# Standalone_Kaleidoscope_8085_MPU_BOARD_V.net
KiCad netlist of a schematic drawn in EAGLE
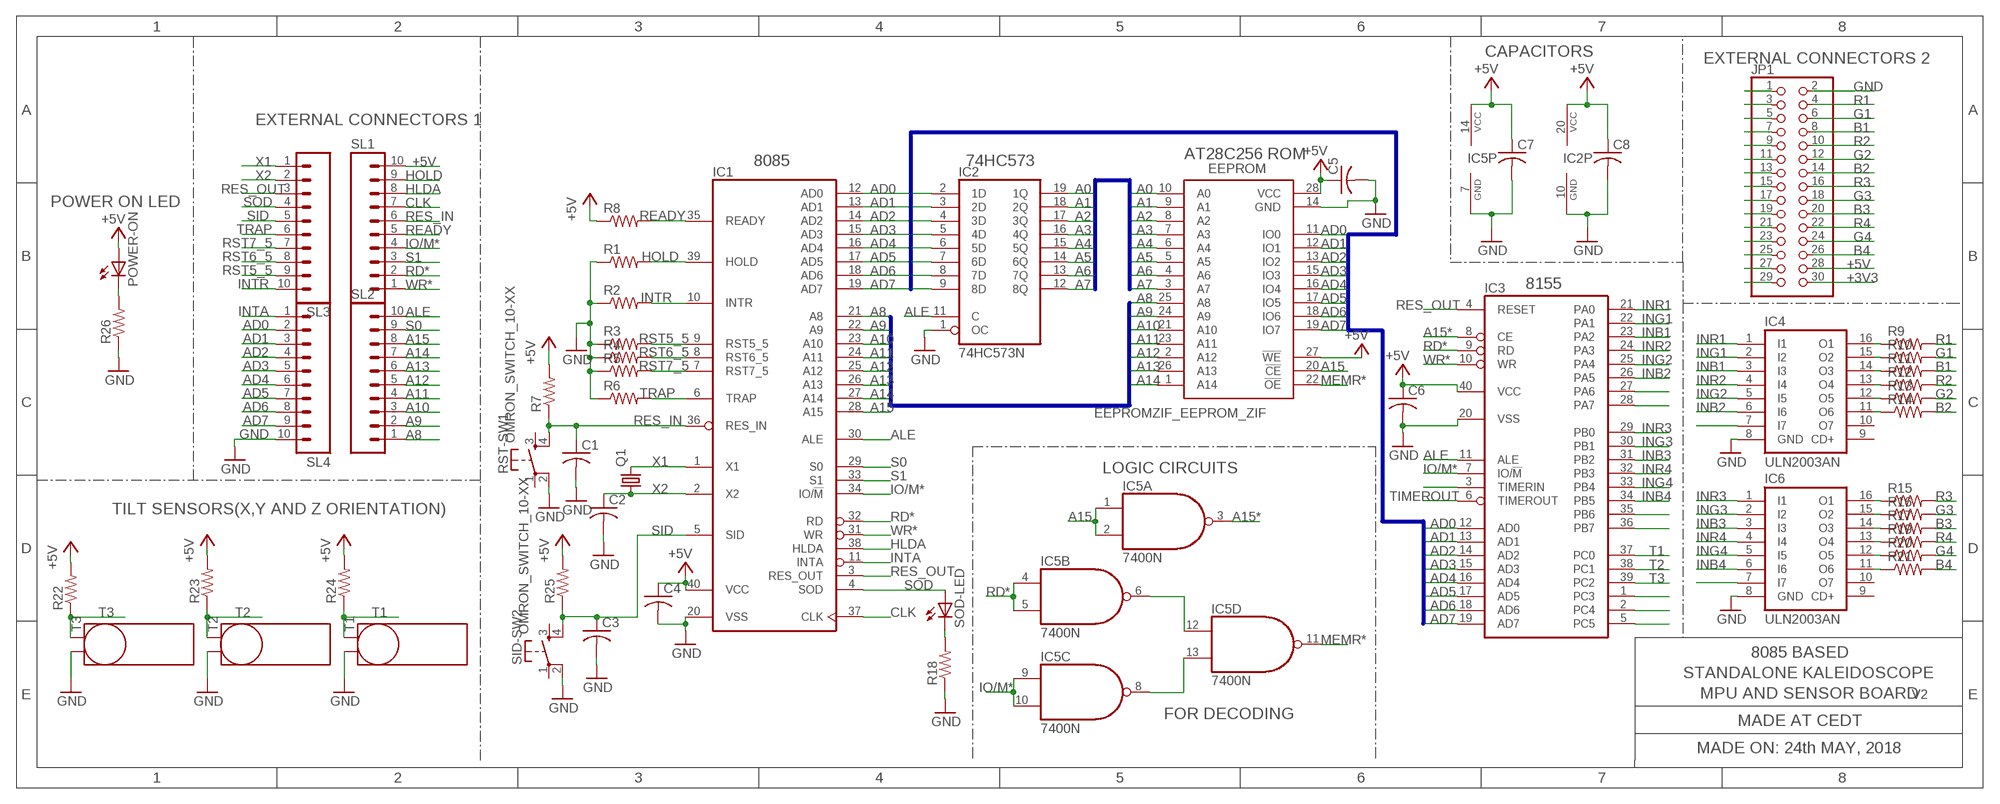
[diagram p0: schematic, sheet 1]

(export (version "E")
  (design (tool "Eeschema 10.0.6"))
  (components
    (comp (ref "C1")
      (value "C-USC0805K")
      (footprint "eagle-import:C0805K")
      (libsource (lib "eagle-import") (part "C-USC0805K"))
    )
    (comp (ref "C2")
      (value "C-USC0805K")
      (footprint "eagle-import:C0805K")
      (libsource (lib "eagle-import") (part "C-USC0805K"))
    )
    (comp (ref "C3")
      (value "C-USC0805K")
      (footprint "eagle-import:C0805K")
      (libsource (lib "eagle-import") (part "C-USC0805K"))
    )
    (comp (ref "C4")
      (value "C-USC0805K")
      (footprint "eagle-import:C0805K")
      (libsource (lib "eagle-import") (part "C-USC0805K"))
    )
    (comp (ref "C5")
      (value "C-USC0805K")
      (footprint "eagle-import:C0805K")
      (libsource (lib "eagle-import") (part "C-USC0805K"))
    )
    (comp (ref "C6")
      (value "C-USC0805K")
      (footprint "eagle-import:C0805K")
      (libsource (lib "eagle-import") (part "C-USC0805K"))
    )
    (comp (ref "C7")
      (value "C-USC0805")
      (footprint "eagle-import:C0805")
      (libsource (lib "eagle-import") (part "C-USC0805"))
    )
    (comp (ref "C8")
      (value "C-USC0805")
      (footprint "eagle-import:C0805")
      (libsource (lib "eagle-import") (part "C-USC0805"))
    )
    (comp (ref "EEPROM")
      (value "EEPROMZIF_EEPROM_ZIF")
      (footprint "eagle-import:EEPROMZIF_DIL28-6-ZIF_SOCKET")
      (libsource (lib "eagle-import") (part "EEPROMZIF_EEPROM_ZIF"))
    )
    (comp (ref "IC1")
      (value "8085")
      (footprint "eagle-import:DIL40")
      (libsource (lib "eagle-import") (part "8085"))
    )
    (comp (ref "IC2")
      (value "74HC573N")
      (footprint "eagle-import:DIL20")
      (libsource (lib "eagle-import") (part "74573NHC"))
    )
    (comp (ref "IC3")
      (value "8155")
      (footprint "eagle-import:DIL40")
      (libsource (lib "eagle-import") (part "8155"))
    )
    (comp (ref "IC4")
      (value "ULN2003AN")
      (footprint "eagle-import:DIL16")
      (libsource (lib "eagle-import") (part "ULN2003AN"))
    )
    (comp (ref "IC5")
      (value "7400N")
      (footprint "eagle-import:DIL14")
      (libsource (lib "eagle-import") (part "7400N"))
    )
    (comp (ref "IC6")
      (value "ULN2003AN")
      (footprint "eagle-import:DIL16")
      (libsource (lib "eagle-import") (part "ULN2003AN"))
    )
    (comp (ref "JP1")
      (value "PINHD-2X15")
      (footprint "eagle-import:2X15")
      (libsource (lib "eagle-import") (part "PINHD-2X15"))
    )
    (comp (ref "POWER-ON")
      (value "LEDCHIP-LED0805")
      (footprint "eagle-import:CHIP-LED0805")
      (libsource (lib "eagle-import") (part "LEDCHIP-LED0805"))
    )
    (comp (ref "Q1")
      (value "CEDT_JANUARY_2015_V5_A_CRYSTALHC49US")
      (footprint "eagle-import:CEDT_JANUARY_2015_V5_A_HC49US")
      (libsource (lib "eagle-import") (part "CEDT_JANUARY_2015_V5_A_CRYSTALHC49US"))
    )
    (comp (ref "R1")
      (value "R-US_R0805")
      (footprint "eagle-import:R0805")
      (libsource (lib "eagle-import") (part "R-US_R0805"))
    )
    (comp (ref "R2")
      (value "R-US_R0805")
      (footprint "eagle-import:R0805")
      (libsource (lib "eagle-import") (part "R-US_R0805"))
    )
    (comp (ref "R3")
      (value "R-US_R0805")
      (footprint "eagle-import:R0805")
      (libsource (lib "eagle-import") (part "R-US_R0805"))
    )
    (comp (ref "R4")
      (value "R-US_R0805")
      (footprint "eagle-import:R0805")
      (libsource (lib "eagle-import") (part "R-US_R0805"))
    )
    (comp (ref "R5")
      (value "R-US_R0805")
      (footprint "eagle-import:R0805")
      (libsource (lib "eagle-import") (part "R-US_R0805"))
    )
    (comp (ref "R6")
      (value "R-US_R0805")
      (footprint "eagle-import:R0805")
      (libsource (lib "eagle-import") (part "R-US_R0805"))
    )
    (comp (ref "R7")
      (value "R-US_R0805")
      (footprint "eagle-import:R0805")
      (libsource (lib "eagle-import") (part "R-US_R0805"))
    )
    (comp (ref "R8")
      (value "R-US_R0805")
      (footprint "eagle-import:R0805")
      (libsource (lib "eagle-import") (part "R-US_R0805"))
    )
    (comp (ref "R9")
      (value "R-US_R0805")
      (footprint "eagle-import:R0805")
      (libsource (lib "eagle-import") (part "R-US_R0805"))
    )
    (comp (ref "R10")
      (value "R-US_R0805")
      (footprint "eagle-import:R0805")
      (libsource (lib "eagle-import") (part "R-US_R0805"))
    )
    (comp (ref "R11")
      (value "R-US_R0805")
      (footprint "eagle-import:R0805")
      (libsource (lib "eagle-import") (part "R-US_R0805"))
    )
    (comp (ref "R12")
      (value "R-US_R0805")
      (footprint "eagle-import:R0805")
      (libsource (lib "eagle-import") (part "R-US_R0805"))
    )
    (comp (ref "R13")
      (value "R-US_R0805")
      (footprint "eagle-import:R0805")
      (libsource (lib "eagle-import") (part "R-US_R0805"))
    )
    (comp (ref "R14")
      (value "R-US_R0805")
      (footprint "eagle-import:R0805")
      (libsource (lib "eagle-import") (part "R-US_R0805"))
    )
    (comp (ref "R15")
      (value "R-US_R0805")
      (footprint "eagle-import:R0805")
      (libsource (lib "eagle-import") (part "R-US_R0805"))
    )
    (comp (ref "R16")
      (value "R-US_R0805")
      (footprint "eagle-import:R0805")
      (libsource (lib "eagle-import") (part "R-US_R0805"))
    )
    (comp (ref "R17")
      (value "R-US_R0805")
      (footprint "eagle-import:R0805")
      (libsource (lib "eagle-import") (part "R-US_R0805"))
    )
    (comp (ref "R18")
      (value "R-US_R0805")
      (footprint "eagle-import:R0805")
      (libsource (lib "eagle-import") (part "R-US_R0805"))
    )
    (comp (ref "R19")
      (value "R-US_R0805")
      (footprint "eagle-import:R0805")
      (libsource (lib "eagle-import") (part "R-US_R0805"))
    )
    (comp (ref "R20")
      (value "R-US_R0805")
      (footprint "eagle-import:R0805")
      (libsource (lib "eagle-import") (part "R-US_R0805"))
    )
    (comp (ref "R21")
      (value "R-US_R0805")
      (footprint "eagle-import:R0805")
      (libsource (lib "eagle-import") (part "R-US_R0805"))
    )
    (comp (ref "R22")
      (value "R-US_R0805")
      (footprint "eagle-import:R0805")
      (libsource (lib "eagle-import") (part "R-US_R0805"))
    )
    (comp (ref "R23")
      (value "R-US_R0805")
      (footprint "eagle-import:R0805")
      (libsource (lib "eagle-import") (part "R-US_R0805"))
    )
    (comp (ref "R24")
      (value "R-US_R0805")
      (footprint "eagle-import:R0805")
      (libsource (lib "eagle-import") (part "R-US_R0805"))
    )
    (comp (ref "R25")
      (value "R-US_R0805")
      (footprint "eagle-import:R0805")
      (libsource (lib "eagle-import") (part "R-US_R0805"))
    )
    (comp (ref "R26")
      (value "R-US_R0805")
      (footprint "eagle-import:R0805")
      (libsource (lib "eagle-import") (part "R-US_R0805"))
    )
    (comp (ref "RST-SW1")
      (value "OMRON_SWITCH_10-XX")
      (footprint "eagle-import:B3F-10XX")
      (libsource (lib "eagle-import") (part "OMRON_SWITCH_10-XX"))
    )
    (comp (ref "SID-SW2")
      (value "OMRON_SWITCH_10-XX")
      (footprint "eagle-import:B3F-10XX")
      (libsource (lib "eagle-import") (part "OMRON_SWITCH_10-XX"))
    )
    (comp (ref "SL1")
      (value "CON-AMP-QUICK_M10")
      (footprint "eagle-import:CON-AMP-QUICK_10P")
      (libsource (lib "eagle-import") (part "CON-AMP-QUICK_M10"))
    )
    (comp (ref "SL2")
      (value "CON-AMP-QUICK_M10")
      (footprint "eagle-import:CON-AMP-QUICK_10P")
      (libsource (lib "eagle-import") (part "CON-AMP-QUICK_M10"))
    )
    (comp (ref "SL3")
      (value "CON-AMP-QUICK_M10")
      (footprint "eagle-import:CON-AMP-QUICK_10P")
      (libsource (lib "eagle-import") (part "CON-AMP-QUICK_M10"))
    )
    (comp (ref "SL4")
      (value "CON-AMP-QUICK_M10")
      (footprint "eagle-import:CON-AMP-QUICK_10P")
      (libsource (lib "eagle-import") (part "CON-AMP-QUICK_M10"))
    )
    (comp (ref "SOD-LED")
      (value "LEDCHIP-LED0805")
      (footprint "eagle-import:CHIP-LED0805")
      (libsource (lib "eagle-import") (part "LEDCHIP-LED0805"))
    )
    (comp (ref "T1")
      (value "TILTSENSORE2.5-7")
      (footprint "eagle-import:TILTSENSOR")
      (libsource (lib "eagle-import") (part "TILTSENSORE2.5-7"))
    )
    (comp (ref "T2")
      (value "TILTSENSORE2.5-7")
      (footprint "eagle-import:TILTSENSOR")
      (libsource (lib "eagle-import") (part "TILTSENSORE2.5-7"))
    )
    (comp (ref "T3")
      (value "TILTSENSORE2.5-7")
      (footprint "eagle-import:TILTSENSOR")
      (libsource (lib "eagle-import") (part "TILTSENSORE2.5-7"))
    )
  )
  (nets
    (net (code "1") (name "+5V") (class "Default")
      (node (ref "C4") (pin "1") (pinfunction "1_1") (pintype "passive"))
      (node (ref "C5") (pin "1") (pinfunction "1_1") (pintype "passive"))
      (node (ref "C6") (pin "1") (pinfunction "1_1") (pintype "passive"))
      (node (ref "C7") (pin "1") (pinfunction "1_1") (pintype "passive"))
      (node (ref "C8") (pin "1") (pinfunction "1_1") (pintype "passive"))
      (node (ref "EEPROM") (pin "27") (pinfunction "~{WE}_27") (pintype "bidirectional"))
      (node (ref "EEPROM") (pin "28") (pinfunction "VCC_28") (pintype "bidirectional"))
      (node (ref "IC1") (pin "40") (pinfunction "VCC_40") (pintype "power_in"))
      (node (ref "IC2") (pin "20") (pinfunction "VCC_20") (pintype "power_in"))
      (node (ref "IC3") (pin "40") (pinfunction "VCC_40") (pintype "power_in"))
      (node (ref "IC5") (pin "14") (pinfunction "VCC_14") (pintype "power_in"))
      (node (ref "JP1") (pin "27") (pinfunction "27_27") (pintype "passive"))
      (node (ref "JP1") (pin "28") (pinfunction "28_28") (pintype "passive"))
      (node (ref "POWER-ON") (pin "A") (pinfunction "A_A") (pintype "passive"))
      (node (ref "R22") (pin "2") (pinfunction "2_2") (pintype "passive"))
      (node (ref "R23") (pin "2") (pinfunction "2_2") (pintype "passive"))
      (node (ref "R24") (pin "2") (pinfunction "2_2") (pintype "passive"))
      (node (ref "R25") (pin "2") (pinfunction "2_2") (pintype "passive"))
      (node (ref "R7") (pin "2") (pinfunction "2_2") (pintype "passive"))
      (node (ref "R8") (pin "1") (pinfunction "1_1") (pintype "passive"))
      (node (ref "SL1") (pin "10") (pinfunction "10_10") (pintype "passive"))
    )
    (net (code "2") (name "/+3V3") (class "Default")
      (node (ref "JP1") (pin "29") (pinfunction "29_29") (pintype "passive"))
      (node (ref "JP1") (pin "30") (pinfunction "30_30") (pintype "passive"))
    )
    (net (code "3") (name "/A0") (class "Default")
      (node (ref "EEPROM") (pin "10") (pinfunction "A0_10") (pintype "bidirectional"))
      (node (ref "IC2") (pin "19") (pinfunction "1Q_19") (pintype "tri_state"))
    )
    (net (code "4") (name "/A1") (class "Default")
      (node (ref "EEPROM") (pin "9") (pinfunction "A1_9") (pintype "bidirectional"))
      (node (ref "IC2") (pin "18") (pinfunction "2Q_18") (pintype "tri_state"))
    )
    (net (code "5") (name "/A2") (class "Default")
      (node (ref "EEPROM") (pin "8") (pinfunction "A2_8") (pintype "bidirectional"))
      (node (ref "IC2") (pin "17") (pinfunction "3Q_17") (pintype "tri_state"))
    )
    (net (code "6") (name "/A3") (class "Default")
      (node (ref "EEPROM") (pin "7") (pinfunction "A3_7") (pintype "bidirectional"))
      (node (ref "IC2") (pin "16") (pinfunction "4Q_16") (pintype "tri_state"))
    )
    (net (code "7") (name "/A4") (class "Default")
      (node (ref "EEPROM") (pin "6") (pinfunction "A4_6") (pintype "bidirectional"))
      (node (ref "IC2") (pin "15") (pinfunction "5Q_15") (pintype "tri_state"))
    )
    (net (code "8") (name "/A5") (class "Default")
      (node (ref "EEPROM") (pin "5") (pinfunction "A5_5") (pintype "bidirectional"))
      (node (ref "IC2") (pin "14") (pinfunction "6Q_14") (pintype "tri_state"))
    )
    (net (code "9") (name "/A6") (class "Default")
      (node (ref "EEPROM") (pin "4") (pinfunction "A6_4") (pintype "bidirectional"))
      (node (ref "IC2") (pin "13") (pinfunction "7Q_13") (pintype "tri_state"))
    )
    (net (code "10") (name "/A7") (class "Default")
      (node (ref "EEPROM") (pin "3") (pinfunction "A7_3") (pintype "bidirectional"))
      (node (ref "IC2") (pin "12") (pinfunction "8Q_12") (pintype "tri_state"))
    )
    (net (code "11") (name "/A8") (class "Default")
      (node (ref "EEPROM") (pin "25") (pinfunction "A8_25") (pintype "bidirectional"))
      (node (ref "IC1") (pin "21") (pinfunction "A8_21") (pintype "output"))
      (node (ref "SL2") (pin "1") (pinfunction "1_1") (pintype "passive"))
    )
    (net (code "12") (name "/A9") (class "Default")
      (node (ref "EEPROM") (pin "24") (pinfunction "A9_24") (pintype "bidirectional"))
      (node (ref "IC1") (pin "22") (pinfunction "A9_22") (pintype "output"))
      (node (ref "SL2") (pin "2") (pinfunction "2_2") (pintype "passive"))
    )
    (net (code "13") (name "/A10") (class "Default")
      (node (ref "EEPROM") (pin "21") (pinfunction "A10_21") (pintype "bidirectional"))
      (node (ref "IC1") (pin "23") (pinfunction "A10_23") (pintype "output"))
      (node (ref "SL2") (pin "3") (pinfunction "3_3") (pintype "passive"))
    )
    (net (code "14") (name "/A11") (class "Default")
      (node (ref "EEPROM") (pin "23") (pinfunction "A11_23") (pintype "bidirectional"))
      (node (ref "IC1") (pin "24") (pinfunction "A11_24") (pintype "output"))
      (node (ref "SL2") (pin "4") (pinfunction "4_4") (pintype "passive"))
    )
    (net (code "15") (name "/A12") (class "Default")
      (node (ref "EEPROM") (pin "2") (pinfunction "A12_2") (pintype "bidirectional"))
      (node (ref "IC1") (pin "25") (pinfunction "A12_25") (pintype "output"))
      (node (ref "SL2") (pin "5") (pinfunction "5_5") (pintype "passive"))
    )
    (net (code "16") (name "/A13") (class "Default")
      (node (ref "EEPROM") (pin "26") (pinfunction "A13_26") (pintype "bidirectional"))
      (node (ref "IC1") (pin "26") (pinfunction "A13_26") (pintype "output"))
      (node (ref "SL2") (pin "6") (pinfunction "6_6") (pintype "passive"))
    )
    (net (code "17") (name "/A14") (class "Default")
      (node (ref "EEPROM") (pin "1") (pinfunction "A14_1") (pintype "bidirectional"))
      (node (ref "IC1") (pin "27") (pinfunction "A14_27") (pintype "output"))
      (node (ref "SL2") (pin "7") (pinfunction "7_7") (pintype "passive"))
    )
    (net (code "18") (name "/A15") (class "Default")
      (node (ref "EEPROM") (pin "20") (pinfunction "~{CE}_20") (pintype "bidirectional"))
      (node (ref "IC1") (pin "28") (pinfunction "A15_28") (pintype "output"))
      (node (ref "IC5") (pin "1") (pinfunction "I0_1") (pintype "input"))
      (node (ref "IC5") (pin "2") (pinfunction "I1_2") (pintype "input"))
      (node (ref "SL2") (pin "8") (pinfunction "8_8") (pintype "passive"))
    )
    (net (code "19") (name "/A15*") (class "Default")
      (node (ref "IC3") (pin "8") (pinfunction "CE_8") (pintype "input"))
      (node (ref "IC5") (pin "3") (pinfunction "O_3") (pintype "output"))
    )
    (net (code "20") (name "/AD0") (class "Default")
      (node (ref "EEPROM") (pin "11") (pinfunction "IO0_11") (pintype "bidirectional"))
      (node (ref "IC1") (pin "12") (pinfunction "AD0_12") (pintype "bidirectional"))
      (node (ref "IC2") (pin "2") (pinfunction "1D_2") (pintype "input"))
      (node (ref "IC3") (pin "12") (pinfunction "AD0_12") (pintype "bidirectional"))
      (node (ref "SL4") (pin "2") (pinfunction "2_2") (pintype "passive"))
    )
    (net (code "21") (name "/AD1") (class "Default")
      (node (ref "EEPROM") (pin "12") (pinfunction "IO1_12") (pintype "bidirectional"))
      (node (ref "IC1") (pin "13") (pinfunction "AD1_13") (pintype "bidirectional"))
      (node (ref "IC2") (pin "3") (pinfunction "2D_3") (pintype "input"))
      (node (ref "IC3") (pin "13") (pinfunction "AD1_13") (pintype "bidirectional"))
      (node (ref "SL4") (pin "3") (pinfunction "3_3") (pintype "passive"))
    )
    (net (code "22") (name "/AD2") (class "Default")
      (node (ref "EEPROM") (pin "13") (pinfunction "IO2_13") (pintype "bidirectional"))
      (node (ref "IC1") (pin "14") (pinfunction "AD2_14") (pintype "bidirectional"))
      (node (ref "IC2") (pin "4") (pinfunction "3D_4") (pintype "input"))
      (node (ref "IC3") (pin "14") (pinfunction "AD2_14") (pintype "bidirectional"))
      (node (ref "SL4") (pin "4") (pinfunction "4_4") (pintype "passive"))
    )
    (net (code "23") (name "/AD3") (class "Default")
      (node (ref "EEPROM") (pin "15") (pinfunction "IO3_15") (pintype "bidirectional"))
      (node (ref "IC1") (pin "15") (pinfunction "AD3_15") (pintype "bidirectional"))
      (node (ref "IC2") (pin "5") (pinfunction "4D_5") (pintype "input"))
      (node (ref "IC3") (pin "15") (pinfunction "AD3_15") (pintype "bidirectional"))
      (node (ref "SL4") (pin "5") (pinfunction "5_5") (pintype "passive"))
    )
    (net (code "24") (name "/AD4") (class "Default")
      (node (ref "EEPROM") (pin "16") (pinfunction "IO4_16") (pintype "bidirectional"))
      (node (ref "IC1") (pin "16") (pinfunction "AD4_16") (pintype "bidirectional"))
      (node (ref "IC2") (pin "6") (pinfunction "5D_6") (pintype "input"))
      (node (ref "IC3") (pin "16") (pinfunction "AD4_16") (pintype "bidirectional"))
      (node (ref "SL4") (pin "6") (pinfunction "6_6") (pintype "passive"))
    )
    (net (code "25") (name "/AD5") (class "Default")
      (node (ref "EEPROM") (pin "17") (pinfunction "IO5_17") (pintype "bidirectional"))
      (node (ref "IC1") (pin "17") (pinfunction "AD5_17") (pintype "bidirectional"))
      (node (ref "IC2") (pin "7") (pinfunction "6D_7") (pintype "input"))
      (node (ref "IC3") (pin "17") (pinfunction "AD5_17") (pintype "bidirectional"))
      (node (ref "SL4") (pin "7") (pinfunction "7_7") (pintype "passive"))
    )
    (net (code "26") (name "/AD6") (class "Default")
      (node (ref "EEPROM") (pin "18") (pinfunction "IO6_18") (pintype "bidirectional"))
      (node (ref "IC1") (pin "18") (pinfunction "AD6_18") (pintype "bidirectional"))
      (node (ref "IC2") (pin "8") (pinfunction "7D_8") (pintype "input"))
      (node (ref "IC3") (pin "18") (pinfunction "AD6_18") (pintype "bidirectional"))
      (node (ref "SL4") (pin "8") (pinfunction "8_8") (pintype "passive"))
    )
    (net (code "27") (name "/AD7") (class "Default")
      (node (ref "EEPROM") (pin "19") (pinfunction "IO7_19") (pintype "bidirectional"))
      (node (ref "IC1") (pin "19") (pinfunction "AD7_19") (pintype "bidirectional"))
      (node (ref "IC2") (pin "9") (pinfunction "8D_9") (pintype "input"))
      (node (ref "IC3") (pin "19") (pinfunction "AD7_19") (pintype "bidirectional"))
      (node (ref "SL4") (pin "9") (pinfunction "9_9") (pintype "passive"))
    )
    (net (code "28") (name "/ALE") (class "Default")
      (node (ref "IC1") (pin "30") (pinfunction "ALE_30") (pintype "output"))
      (node (ref "IC2") (pin "11") (pinfunction "C_11") (pintype "input"))
      (node (ref "IC3") (pin "11") (pinfunction "ALE_11") (pintype "input"))
      (node (ref "SL2") (pin "10") (pinfunction "10_10") (pintype "passive"))
    )
    (net (code "29") (name "/B1") (class "Default")
      (node (ref "JP1") (pin "7") (pinfunction "7_7") (pintype "passive"))
      (node (ref "JP1") (pin "8") (pinfunction "8_8") (pintype "passive"))
      (node (ref "R11") (pin "2") (pinfunction "2_2") (pintype "passive"))
    )
    (net (code "30") (name "/B2") (class "Default")
      (node (ref "JP1") (pin "13") (pinfunction "13_13") (pintype "passive"))
      (node (ref "JP1") (pin "14") (pinfunction "14_14") (pintype "passive"))
      (node (ref "R14") (pin "2") (pinfunction "2_2") (pintype "passive"))
    )
    (net (code "31") (name "/B3") (class "Default")
      (node (ref "JP1") (pin "19") (pinfunction "19_19") (pintype "passive"))
      (node (ref "JP1") (pin "20") (pinfunction "20_20") (pintype "passive"))
      (node (ref "R17") (pin "2") (pinfunction "2_2") (pintype "passive"))
    )
    (net (code "32") (name "/B4") (class "Default")
      (node (ref "JP1") (pin "25") (pinfunction "25_25") (pintype "passive"))
      (node (ref "JP1") (pin "26") (pinfunction "26_26") (pintype "passive"))
      (node (ref "R21") (pin "2") (pinfunction "2_2") (pintype "passive"))
    )
    (net (code "33") (name "/CLK") (class "Default")
      (node (ref "IC1") (pin "37") (pinfunction "CLK_37") (pintype "output"))
      (node (ref "SL1") (pin "7") (pinfunction "7_7") (pintype "passive"))
    )
    (net (code "34") (name "/G1") (class "Default")
      (node (ref "JP1") (pin "5") (pinfunction "5_5") (pintype "passive"))
      (node (ref "JP1") (pin "6") (pinfunction "6_6") (pintype "passive"))
      (node (ref "R10") (pin "2") (pinfunction "2_2") (pintype "passive"))
    )
    (net (code "35") (name "/G2") (class "Default")
      (node (ref "JP1") (pin "11") (pinfunction "11_11") (pintype "passive"))
      (node (ref "JP1") (pin "12") (pinfunction "12_12") (pintype "passive"))
      (node (ref "R13") (pin "2") (pinfunction "2_2") (pintype "passive"))
    )
    (net (code "36") (name "/G3") (class "Default")
      (node (ref "JP1") (pin "17") (pinfunction "17_17") (pintype "passive"))
      (node (ref "JP1") (pin "18") (pinfunction "18_18") (pintype "passive"))
      (node (ref "R16") (pin "2") (pinfunction "2_2") (pintype "passive"))
    )
    (net (code "37") (name "/G4") (class "Default")
      (node (ref "JP1") (pin "23") (pinfunction "23_23") (pintype "passive"))
      (node (ref "JP1") (pin "24") (pinfunction "24_24") (pintype "passive"))
      (node (ref "R20") (pin "2") (pinfunction "2_2") (pintype "passive"))
    )
    (net (code "38") (name "/HLDA") (class "Default")
      (node (ref "IC1") (pin "38") (pinfunction "HLDA_38") (pintype "output"))
      (node (ref "SL1") (pin "8") (pinfunction "8_8") (pintype "passive"))
    )
    (net (code "39") (name "/HOLD") (class "Default")
      (node (ref "IC1") (pin "39") (pinfunction "HOLD_39") (pintype "input"))
      (node (ref "R1") (pin "2") (pinfunction "2_2") (pintype "passive"))
      (node (ref "SL1") (pin "9") (pinfunction "9_9") (pintype "passive"))
    )
    (net (code "40") (name "/INB1") (class "Default")
      (node (ref "IC3") (pin "23") (pinfunction "PA2_23") (pintype "bidirectional"))
      (node (ref "IC4") (pin "3") (pinfunction "I3_3") (pintype "input"))
    )
    (net (code "41") (name "/INB2") (class "Default")
      (node (ref "IC3") (pin "26") (pinfunction "PA5_26") (pintype "bidirectional"))
      (node (ref "IC4") (pin "6") (pinfunction "I6_6") (pintype "input"))
    )
    (net (code "42") (name "/INB3") (class "Default")
      (node (ref "IC3") (pin "31") (pinfunction "PB2_31") (pintype "bidirectional"))
      (node (ref "IC6") (pin "3") (pinfunction "I3_3") (pintype "input"))
    )
    (net (code "43") (name "/INB4") (class "Default")
      (node (ref "IC3") (pin "34") (pinfunction "PB5_34") (pintype "bidirectional"))
      (node (ref "IC6") (pin "6") (pinfunction "I6_6") (pintype "input"))
    )
    (net (code "44") (name "/ING1") (class "Default")
      (node (ref "IC3") (pin "22") (pinfunction "PA1_22") (pintype "bidirectional"))
      (node (ref "IC4") (pin "2") (pinfunction "I2_2") (pintype "input"))
    )
    (net (code "45") (name "/ING2") (class "Default")
      (node (ref "IC3") (pin "25") (pinfunction "PA4_25") (pintype "bidirectional"))
      (node (ref "IC4") (pin "5") (pinfunction "I5_5") (pintype "input"))
    )
    (net (code "46") (name "/ING3") (class "Default")
      (node (ref "IC3") (pin "30") (pinfunction "PB1_30") (pintype "bidirectional"))
      (node (ref "IC6") (pin "2") (pinfunction "I2_2") (pintype "input"))
    )
    (net (code "47") (name "/ING4") (class "Default")
      (node (ref "IC3") (pin "33") (pinfunction "PB4_33") (pintype "bidirectional"))
      (node (ref "IC6") (pin "5") (pinfunction "I5_5") (pintype "input"))
    )
    (net (code "48") (name "/INR1") (class "Default")
      (node (ref "IC3") (pin "21") (pinfunction "PA0_21") (pintype "bidirectional"))
      (node (ref "IC4") (pin "1") (pinfunction "I1_1") (pintype "input"))
    )
    (net (code "49") (name "/INR2") (class "Default")
      (node (ref "IC3") (pin "24") (pinfunction "PA3_24") (pintype "bidirectional"))
      (node (ref "IC4") (pin "4") (pinfunction "I4_4") (pintype "input"))
    )
    (net (code "50") (name "/INR3") (class "Default")
      (node (ref "IC3") (pin "29") (pinfunction "PB0_29") (pintype "bidirectional"))
      (node (ref "IC6") (pin "1") (pinfunction "I1_1") (pintype "input"))
    )
    (net (code "51") (name "/INR4") (class "Default")
      (node (ref "IC3") (pin "32") (pinfunction "PB3_32") (pintype "bidirectional"))
      (node (ref "IC6") (pin "4") (pinfunction "I4_4") (pintype "input"))
    )
    (net (code "52") (name "/INTA") (class "Default")
      (node (ref "IC1") (pin "11") (pinfunction "INTA_11") (pintype "output"))
      (node (ref "SL4") (pin "1") (pinfunction "1_1") (pintype "passive"))
    )
    (net (code "53") (name "/INTR") (class "Default")
      (node (ref "IC1") (pin "10") (pinfunction "INTR_10") (pintype "input"))
      (node (ref "R2") (pin "2") (pinfunction "2_2") (pintype "passive"))
      (node (ref "SL3") (pin "10") (pinfunction "10_10") (pintype "passive"))
    )
    (net (code "54") (name "/IO{slash}M*") (class "Default")
      (node (ref "IC1") (pin "34") (pinfunction "IO/~{M}_34") (pintype "output"))
      (node (ref "IC3") (pin "7") (pinfunction "IO/~{M}_7") (pintype "input"))
      (node (ref "IC5") (pin "10") (pinfunction "I1_10") (pintype "input"))
      (node (ref "IC5") (pin "9") (pinfunction "I0_9") (pintype "input"))
      (node (ref "SL1") (pin "4") (pinfunction "4_4") (pintype "passive"))
    )
    (net (code "55") (name "/MEMR*") (class "Default")
      (node (ref "EEPROM") (pin "22") (pinfunction "~{OE}_22") (pintype "bidirectional"))
      (node (ref "IC5") (pin "11") (pinfunction "O_11") (pintype "output"))
    )
    (net (code "56") (name "/R1") (class "Default")
      (node (ref "JP1") (pin "3") (pinfunction "3_3") (pintype "passive"))
      (node (ref "JP1") (pin "4") (pinfunction "4_4") (pintype "passive"))
      (node (ref "R9") (pin "2") (pinfunction "2_2") (pintype "passive"))
    )
    (net (code "57") (name "/R2") (class "Default")
      (node (ref "JP1") (pin "10") (pinfunction "10_10") (pintype "passive"))
      (node (ref "JP1") (pin "9") (pinfunction "9_9") (pintype "passive"))
      (node (ref "R12") (pin "2") (pinfunction "2_2") (pintype "passive"))
    )
    (net (code "58") (name "/R3") (class "Default")
      (node (ref "JP1") (pin "15") (pinfunction "15_15") (pintype "passive"))
      (node (ref "JP1") (pin "16") (pinfunction "16_16") (pintype "passive"))
      (node (ref "R15") (pin "2") (pinfunction "2_2") (pintype "passive"))
    )
    (net (code "59") (name "/R4") (class "Default")
      (node (ref "JP1") (pin "21") (pinfunction "21_21") (pintype "passive"))
      (node (ref "JP1") (pin "22") (pinfunction "22_22") (pintype "passive"))
      (node (ref "R19") (pin "2") (pinfunction "2_2") (pintype "passive"))
    )
    (net (code "60") (name "/RD*") (class "Default")
      (node (ref "IC1") (pin "32") (pinfunction "RD_32") (pintype "output"))
      (node (ref "IC3") (pin "9") (pinfunction "RD_9") (pintype "input"))
      (node (ref "IC5") (pin "4") (pinfunction "I0_4") (pintype "input"))
      (node (ref "IC5") (pin "5") (pinfunction "I1_5") (pintype "input"))
      (node (ref "SL1") (pin "2") (pinfunction "2_2") (pintype "passive"))
    )
    (net (code "61") (name "/READY") (class "Default")
      (node (ref "IC1") (pin "35") (pinfunction "READY_35") (pintype "input"))
      (node (ref "R8") (pin "2") (pinfunction "2_2") (pintype "passive"))
      (node (ref "SL1") (pin "5") (pinfunction "5_5") (pintype "passive"))
    )
    (net (code "62") (name "/RES_IN") (class "Default")
      (node (ref "C1") (pin "1") (pinfunction "1_1") (pintype "passive"))
      (node (ref "IC1") (pin "36") (pinfunction "RES_IN_36") (pintype "input"))
      (node (ref "R7") (pin "1") (pinfunction "1_1") (pintype "passive"))
      (node (ref "RST-SW1") (pin "4") (pinfunction "S1_4") (pintype "passive"))
      (node (ref "SL1") (pin "6") (pinfunction "6_6") (pintype "passive"))
    )
    (net (code "63") (name "/RES_OUT") (class "Default")
      (node (ref "IC1") (pin "3") (pinfunction "RES_OUT_3") (pintype "output"))
      (node (ref "IC3") (pin "4") (pinfunction "RESET_4") (pintype "input"))
      (node (ref "SL3") (pin "3") (pinfunction "3_3") (pintype "passive"))
    )
    (net (code "64") (name "/RST5_5") (class "Default")
      (node (ref "IC1") (pin "9") (pinfunction "RST5_5_9") (pintype "input"))
      (node (ref "R3") (pin "2") (pinfunction "2_2") (pintype "passive"))
      (node (ref "SL3") (pin "9") (pinfunction "9_9") (pintype "passive"))
    )
    (net (code "65") (name "/RST6_5") (class "Default")
      (node (ref "IC1") (pin "8") (pinfunction "RST6_5_8") (pintype "input"))
      (node (ref "R4") (pin "2") (pinfunction "2_2") (pintype "passive"))
      (node (ref "SL3") (pin "8") (pinfunction "8_8") (pintype "passive"))
    )
    (net (code "66") (name "/RST7_5") (class "Default")
      (node (ref "IC1") (pin "7") (pinfunction "RST7_5_7") (pintype "input"))
      (node (ref "R5") (pin "2") (pinfunction "2_2") (pintype "passive"))
      (node (ref "SL3") (pin "7") (pinfunction "7_7") (pintype "passive"))
    )
    (net (code "67") (name "/S0") (class "Default")
      (node (ref "IC1") (pin "29") (pinfunction "S0_29") (pintype "output"))
      (node (ref "SL2") (pin "9") (pinfunction "9_9") (pintype "passive"))
    )
    (net (code "68") (name "/S1") (class "Default")
      (node (ref "IC1") (pin "33") (pinfunction "S1_33") (pintype "output"))
      (node (ref "SL1") (pin "3") (pinfunction "3_3") (pintype "passive"))
    )
    (net (code "69") (name "/SID") (class "Default")
      (node (ref "C3") (pin "1") (pinfunction "1_1") (pintype "passive"))
      (node (ref "IC1") (pin "5") (pinfunction "SID_5") (pintype "input"))
      (node (ref "R25") (pin "1") (pinfunction "1_1") (pintype "passive"))
      (node (ref "SID-SW2") (pin "4") (pinfunction "S1_4") (pintype "passive"))
      (node (ref "SL3") (pin "5") (pinfunction "5_5") (pintype "passive"))
    )
    (net (code "70") (name "/SOD") (class "Default")
      (node (ref "IC1") (pin "4") (pinfunction "SOD_4") (pintype "output"))
      (node (ref "SL3") (pin "4") (pinfunction "4_4") (pintype "passive"))
      (node (ref "SOD-LED") (pin "A") (pinfunction "A_A") (pintype "passive"))
    )
    (net (code "71") (name "/T1") (class "Default")
      (node (ref "IC3") (pin "37") (pinfunction "PC0_37") (pintype "bidirectional"))
      (node (ref "R24") (pin "1") (pinfunction "1_1") (pintype "passive"))
      (node (ref "T1") (pin "+") (pinfunction "+_+") (pintype "passive"))
    )
    (net (code "72") (name "/T2") (class "Default")
      (node (ref "IC3") (pin "38") (pinfunction "PC1_38") (pintype "bidirectional"))
      (node (ref "R23") (pin "1") (pinfunction "1_1") (pintype "passive"))
      (node (ref "T2") (pin "+") (pinfunction "+_+") (pintype "passive"))
    )
    (net (code "73") (name "/T3") (class "Default")
      (node (ref "IC3") (pin "39") (pinfunction "PC2_39") (pintype "bidirectional"))
      (node (ref "R22") (pin "1") (pinfunction "1_1") (pintype "passive"))
      (node (ref "T3") (pin "+") (pinfunction "+_+") (pintype "passive"))
    )
    (net (code "74") (name "/TIMEROUT") (class "Default")
      (node (ref "IC3") (pin "6") (pinfunction "TIMEROUT_6") (pintype "output"))
    )
    (net (code "75") (name "/TRAP") (class "Default")
      (node (ref "IC1") (pin "6") (pinfunction "TRAP_6") (pintype "input"))
      (node (ref "R6") (pin "2") (pinfunction "2_2") (pintype "passive"))
      (node (ref "SL3") (pin "6") (pinfunction "6_6") (pintype "passive"))
    )
    (net (code "76") (name "/WR*") (class "Default")
      (node (ref "IC1") (pin "31") (pinfunction "WR_31") (pintype "output"))
      (node (ref "IC3") (pin "10") (pinfunction "WR_10") (pintype "input"))
      (node (ref "SL1") (pin "1") (pinfunction "1_1") (pintype "passive"))
    )
    (net (code "77") (name "/X1") (class "Default")
      (node (ref "IC1") (pin "1") (pinfunction "X1_1") (pintype "input"))
      (node (ref "Q1") (pin "2") (pinfunction "2_2") (pintype "passive"))
      (node (ref "SL3") (pin "1") (pinfunction "1_1") (pintype "passive"))
    )
    (net (code "78") (name "/X2") (class "Default")
      (node (ref "C2") (pin "1") (pinfunction "1_1") (pintype "passive"))
      (node (ref "IC1") (pin "2") (pinfunction "X2_2") (pintype "input"))
      (node (ref "Q1") (pin "1") (pinfunction "1_1") (pintype "passive"))
      (node (ref "SL3") (pin "2") (pinfunction "2_2") (pintype "passive"))
    )
    (net (code "79") (name "GND") (class "Default")
      (node (ref "C1") (pin "2") (pinfunction "2_2") (pintype "passive"))
      (node (ref "C2") (pin "2") (pinfunction "2_2") (pintype "passive"))
      (node (ref "C3") (pin "2") (pinfunction "2_2") (pintype "passive"))
      (node (ref "C4") (pin "2") (pinfunction "2_2") (pintype "passive"))
      (node (ref "C5") (pin "2") (pinfunction "2_2") (pintype "passive"))
      (node (ref "C6") (pin "2") (pinfunction "2_2") (pintype "passive"))
      (node (ref "C7") (pin "2") (pinfunction "2_2") (pintype "passive"))
      (node (ref "C8") (pin "2") (pinfunction "2_2") (pintype "passive"))
      (node (ref "EEPROM") (pin "14") (pinfunction "GND_14") (pintype "bidirectional"))
      (node (ref "IC1") (pin "20") (pinfunction "VSS_20") (pintype "power_in"))
      (node (ref "IC2") (pin "1") (pinfunction "OC_1") (pintype "input"))
      (node (ref "IC2") (pin "10") (pinfunction "GND_10") (pintype "power_in"))
      (node (ref "IC3") (pin "20") (pinfunction "VSS_20") (pintype "power_in"))
      (node (ref "IC4") (pin "8") (pinfunction "GND_8") (pintype "power_in"))
      (node (ref "IC5") (pin "7") (pinfunction "GND_7") (pintype "power_in"))
      (node (ref "IC6") (pin "8") (pinfunction "GND_8") (pintype "power_in"))
      (node (ref "JP1") (pin "1") (pinfunction "1_1") (pintype "passive"))
      (node (ref "JP1") (pin "2") (pinfunction "2_2") (pintype "passive"))
      (node (ref "R1") (pin "1") (pinfunction "1_1") (pintype "passive"))
      (node (ref "R18") (pin "1") (pinfunction "1_1") (pintype "passive"))
      (node (ref "R2") (pin "1") (pinfunction "1_1") (pintype "passive"))
      (node (ref "R26") (pin "1") (pinfunction "1_1") (pintype "passive"))
      (node (ref "R3") (pin "1") (pinfunction "1_1") (pintype "passive"))
      (node (ref "R4") (pin "1") (pinfunction "1_1") (pintype "passive"))
      (node (ref "R5") (pin "1") (pinfunction "1_1") (pintype "passive"))
      (node (ref "R6") (pin "1") (pinfunction "1_1") (pintype "passive"))
      (node (ref "RST-SW1") (pin "2") (pinfunction "P1_2") (pintype "passive"))
      (node (ref "SID-SW2") (pin "2") (pinfunction "P1_2") (pintype "passive"))
      (node (ref "SL4") (pin "10") (pinfunction "10_10") (pintype "passive"))
      (node (ref "T1") (pin "-") (pinfunction "-_-") (pintype "passive"))
      (node (ref "T2") (pin "-") (pinfunction "-_-") (pintype "passive"))
      (node (ref "T3") (pin "-") (pinfunction "-_-") (pintype "passive"))
    )
    (net (code "80") (name "Net-(IC4-O1)") (class "Default")
      (node (ref "IC4") (pin "16") (pinfunction "O1_16") (pintype "open_collector"))
      (node (ref "R9") (pin "1") (pinfunction "1_1") (pintype "passive"))
    )
    (net (code "81") (name "Net-(IC4-O2)") (class "Default")
      (node (ref "IC4") (pin "15") (pinfunction "O2_15") (pintype "open_collector"))
      (node (ref "R10") (pin "1") (pinfunction "1_1") (pintype "passive"))
    )
    (net (code "82") (name "Net-(IC4-O3)") (class "Default")
      (node (ref "IC4") (pin "14") (pinfunction "O3_14") (pintype "open_collector"))
      (node (ref "R11") (pin "1") (pinfunction "1_1") (pintype "passive"))
    )
    (net (code "83") (name "Net-(IC4-O4)") (class "Default")
      (node (ref "IC4") (pin "13") (pinfunction "O4_13") (pintype "open_collector"))
      (node (ref "R12") (pin "1") (pinfunction "1_1") (pintype "passive"))
    )
    (net (code "84") (name "Net-(IC4-O5)") (class "Default")
      (node (ref "IC4") (pin "12") (pinfunction "O5_12") (pintype "open_collector"))
      (node (ref "R13") (pin "1") (pinfunction "1_1") (pintype "passive"))
    )
    (net (code "85") (name "Net-(IC4-O6)") (class "Default")
      (node (ref "IC4") (pin "11") (pinfunction "O6_11") (pintype "open_collector"))
      (node (ref "R14") (pin "1") (pinfunction "1_1") (pintype "passive"))
    )
    (net (code "86") (name "Net-(IC5B-O)") (class "Default")
      (node (ref "IC5") (pin "12") (pinfunction "I0_12") (pintype "input"))
      (node (ref "IC5") (pin "6") (pinfunction "O_6") (pintype "output"))
    )
    (net (code "87") (name "Net-(IC5C-O)") (class "Default")
      (node (ref "IC5") (pin "13") (pinfunction "I1_13") (pintype "input"))
      (node (ref "IC5") (pin "8") (pinfunction "O_8") (pintype "output"))
    )
    (net (code "88") (name "Net-(IC6-O1)") (class "Default")
      (node (ref "IC6") (pin "16") (pinfunction "O1_16") (pintype "open_collector"))
      (node (ref "R15") (pin "1") (pinfunction "1_1") (pintype "passive"))
    )
    (net (code "89") (name "Net-(IC6-O2)") (class "Default")
      (node (ref "IC6") (pin "15") (pinfunction "O2_15") (pintype "open_collector"))
      (node (ref "R16") (pin "1") (pinfunction "1_1") (pintype "passive"))
    )
    (net (code "90") (name "Net-(IC6-O3)") (class "Default")
      (node (ref "IC6") (pin "14") (pinfunction "O3_14") (pintype "open_collector"))
      (node (ref "R17") (pin "1") (pinfunction "1_1") (pintype "passive"))
    )
    (net (code "91") (name "Net-(IC6-O4)") (class "Default")
      (node (ref "IC6") (pin "13") (pinfunction "O4_13") (pintype "open_collector"))
      (node (ref "R19") (pin "1") (pinfunction "1_1") (pintype "passive"))
    )
    (net (code "92") (name "Net-(IC6-O5)") (class "Default")
      (node (ref "IC6") (pin "12") (pinfunction "O5_12") (pintype "open_collector"))
      (node (ref "R20") (pin "1") (pinfunction "1_1") (pintype "passive"))
    )
    (net (code "93") (name "Net-(IC6-O6)") (class "Default")
      (node (ref "IC6") (pin "11") (pinfunction "O6_11") (pintype "open_collector"))
      (node (ref "R21") (pin "1") (pinfunction "1_1") (pintype "passive"))
    )
    (net (code "94") (name "Net-(POWER-ON-PadC)") (class "Default")
      (node (ref "POWER-ON") (pin "C") (pinfunction "C_C") (pintype "passive"))
      (node (ref "R26") (pin "2") (pinfunction "2_2") (pintype "passive"))
    )
    (net (code "95") (name "Net-(R18-Pad2)") (class "Default")
      (node (ref "R18") (pin "2") (pinfunction "2_2") (pintype "passive"))
      (node (ref "SOD-LED") (pin "C") (pinfunction "C_C") (pintype "passive"))
    )
    (net (code "96") (name "unconnected-(IC3-PA6-Pad27)") (class "Default")
      (node (ref "IC3") (pin "27") (pinfunction "PA6_27") (pintype "bidirectional"))
    )
    (net (code "97") (name "unconnected-(IC3-PA7-Pad28)") (class "Default")
      (node (ref "IC3") (pin "28") (pinfunction "PA7_28") (pintype "bidirectional"))
    )
    (net (code "98") (name "unconnected-(IC3-PB6-Pad35)") (class "Default")
      (node (ref "IC3") (pin "35") (pinfunction "PB6_35") (pintype "bidirectional"))
    )
    (net (code "99") (name "unconnected-(IC3-PB7-Pad36)") (class "Default")
      (node (ref "IC3") (pin "36") (pinfunction "PB7_36") (pintype "bidirectional"))
    )
    (net (code "100") (name "unconnected-(IC3-PC3-Pad1)") (class "Default")
      (node (ref "IC3") (pin "1") (pinfunction "PC3_1") (pintype "bidirectional"))
    )
    (net (code "101") (name "unconnected-(IC3-PC4-Pad2)") (class "Default")
      (node (ref "IC3") (pin "2") (pinfunction "PC4_2") (pintype "bidirectional"))
    )
    (net (code "102") (name "unconnected-(IC3-PC5-Pad5)") (class "Default")
      (node (ref "IC3") (pin "5") (pinfunction "PC5_5") (pintype "bidirectional"))
    )
    (net (code "103") (name "unconnected-(IC3-TIMERIN-Pad3)") (class "Default")
      (node (ref "IC3") (pin "3") (pinfunction "TIMERIN_3") (pintype "input"))
    )
    (net (code "104") (name "unconnected-(IC4-CD+-Pad9)") (class "Default")
      (node (ref "IC4") (pin "9") (pinfunction "CD+_9") (pintype "passive"))
    )
    (net (code "105") (name "unconnected-(IC4-I7-Pad7)") (class "Default")
      (node (ref "IC4") (pin "7") (pinfunction "I7_7") (pintype "input"))
    )
    (net (code "106") (name "unconnected-(IC4-O7-Pad10)") (class "Default")
      (node (ref "IC4") (pin "10") (pinfunction "O7_10") (pintype "open_collector"))
    )
    (net (code "107") (name "unconnected-(IC6-CD+-Pad9)") (class "Default")
      (node (ref "IC6") (pin "9") (pinfunction "CD+_9") (pintype "passive"))
    )
    (net (code "108") (name "unconnected-(IC6-I7-Pad7)") (class "Default")
      (node (ref "IC6") (pin "7") (pinfunction "I7_7") (pintype "input"))
    )
    (net (code "109") (name "unconnected-(IC6-O7-Pad10)") (class "Default")
      (node (ref "IC6") (pin "10") (pinfunction "O7_10") (pintype "open_collector"))
    )
    (net (code "110") (name "unconnected-(RST-SW1-P-Pad1)") (class "Default")
      (node (ref "RST-SW1") (pin "1") (pinfunction "P_1") (pintype "passive"))
    )
    (net (code "111") (name "unconnected-(RST-SW1-S-Pad3)") (class "Default")
      (node (ref "RST-SW1") (pin "3") (pinfunction "S_3") (pintype "passive"))
    )
    (net (code "112") (name "unconnected-(SID-SW2-P-Pad1)") (class "Default")
      (node (ref "SID-SW2") (pin "1") (pinfunction "P_1") (pintype "passive"))
    )
    (net (code "113") (name "unconnected-(SID-SW2-S-Pad3)") (class "Default")
      (node (ref "SID-SW2") (pin "3") (pinfunction "S_3") (pintype "passive"))
    )
  )
)
